# Button-LED.net
KiCad netlist of a schematic drawn in Altium Designer
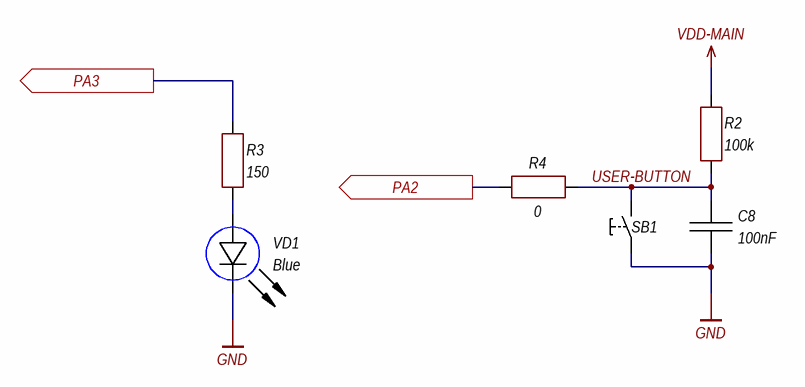
[diagram p0: Button-LED.SchDoc]

(export (version "E")
  (design (tool "Eeschema 10.0.6"))
  (components
    (comp (ref "C8") (value "100nF") (footprint "CH0402C") (libsource (lib "Discrete") (part "Capacitor")))
    (comp (ref "R2") (value "100k") (footprint "CH0402R") (libsource (lib "") (part "Resistor_1")))
    (comp (ref "R3") (value "150") (footprint "CH0402R") (libsource (lib "") (part "Resistor_1")))
    (comp (ref "R4") (value "0") (footprint "CH0402R") (libsource (lib "Discrete") (part "Resistor")))
    (comp (ref "SB1")
      (value "\"Кнопка\"")
      (footprint "BUT: YTS-A017")
      (description "Button, no latching")
      (libsource (lib "Connectors") (part "1-Button"))
    )
    (comp (ref "VD1") (value "Blue") (footprint "CH0402LG") (libsource (lib "Discrete") (part "LED")))
  )
  (nets
    (net (code "1") (name "/PA2") (class "Default")
      (node (ref "R4") (pin "1") (pinfunction "1_1") (pintype "passive"))
    )
    (net (code "2") (name "/PA3") (class "Default")
      (node (ref "R3") (pin "2") (pinfunction "2_2") (pintype "passive"))
    )
    (net (code "3") (name "/USER-BUTTON") (class "Default")
      (node (ref "C8") (pin "2") (pinfunction "2_2") (pintype "passive"))
      (node (ref "R2") (pin "1") (pinfunction "1_1") (pintype "passive"))
      (node (ref "R4") (pin "2") (pinfunction "2_2") (pintype "passive"))
      (node (ref "SB1") (pin "2") (pinfunction "2_2") (pintype "passive"))
    )
    (net (code "4") (name "GND") (class "Default")
      (node (ref "C8") (pin "1") (pinfunction "1_1") (pintype "passive"))
      (node (ref "SB1") (pin "1") (pinfunction "1_1") (pintype "passive"))
      (node (ref "VD1") (pin "2") (pinfunction "C_2") (pintype "passive"))
    )
    (net (code "5") (name "Net-(VD1-A)") (class "Default")
      (node (ref "R3") (pin "1") (pinfunction "1_1") (pintype "passive"))
      (node (ref "VD1") (pin "1") (pinfunction "A_1") (pintype "passive"))
    )
    (net (code "6") (name "VDD-MAIN") (class "Default")
      (node (ref "R2") (pin "2") (pinfunction "2_2") (pintype "passive"))
    )
  )
)
